# Register.net
KiCad netlist of a schematic drawn in EAGLE
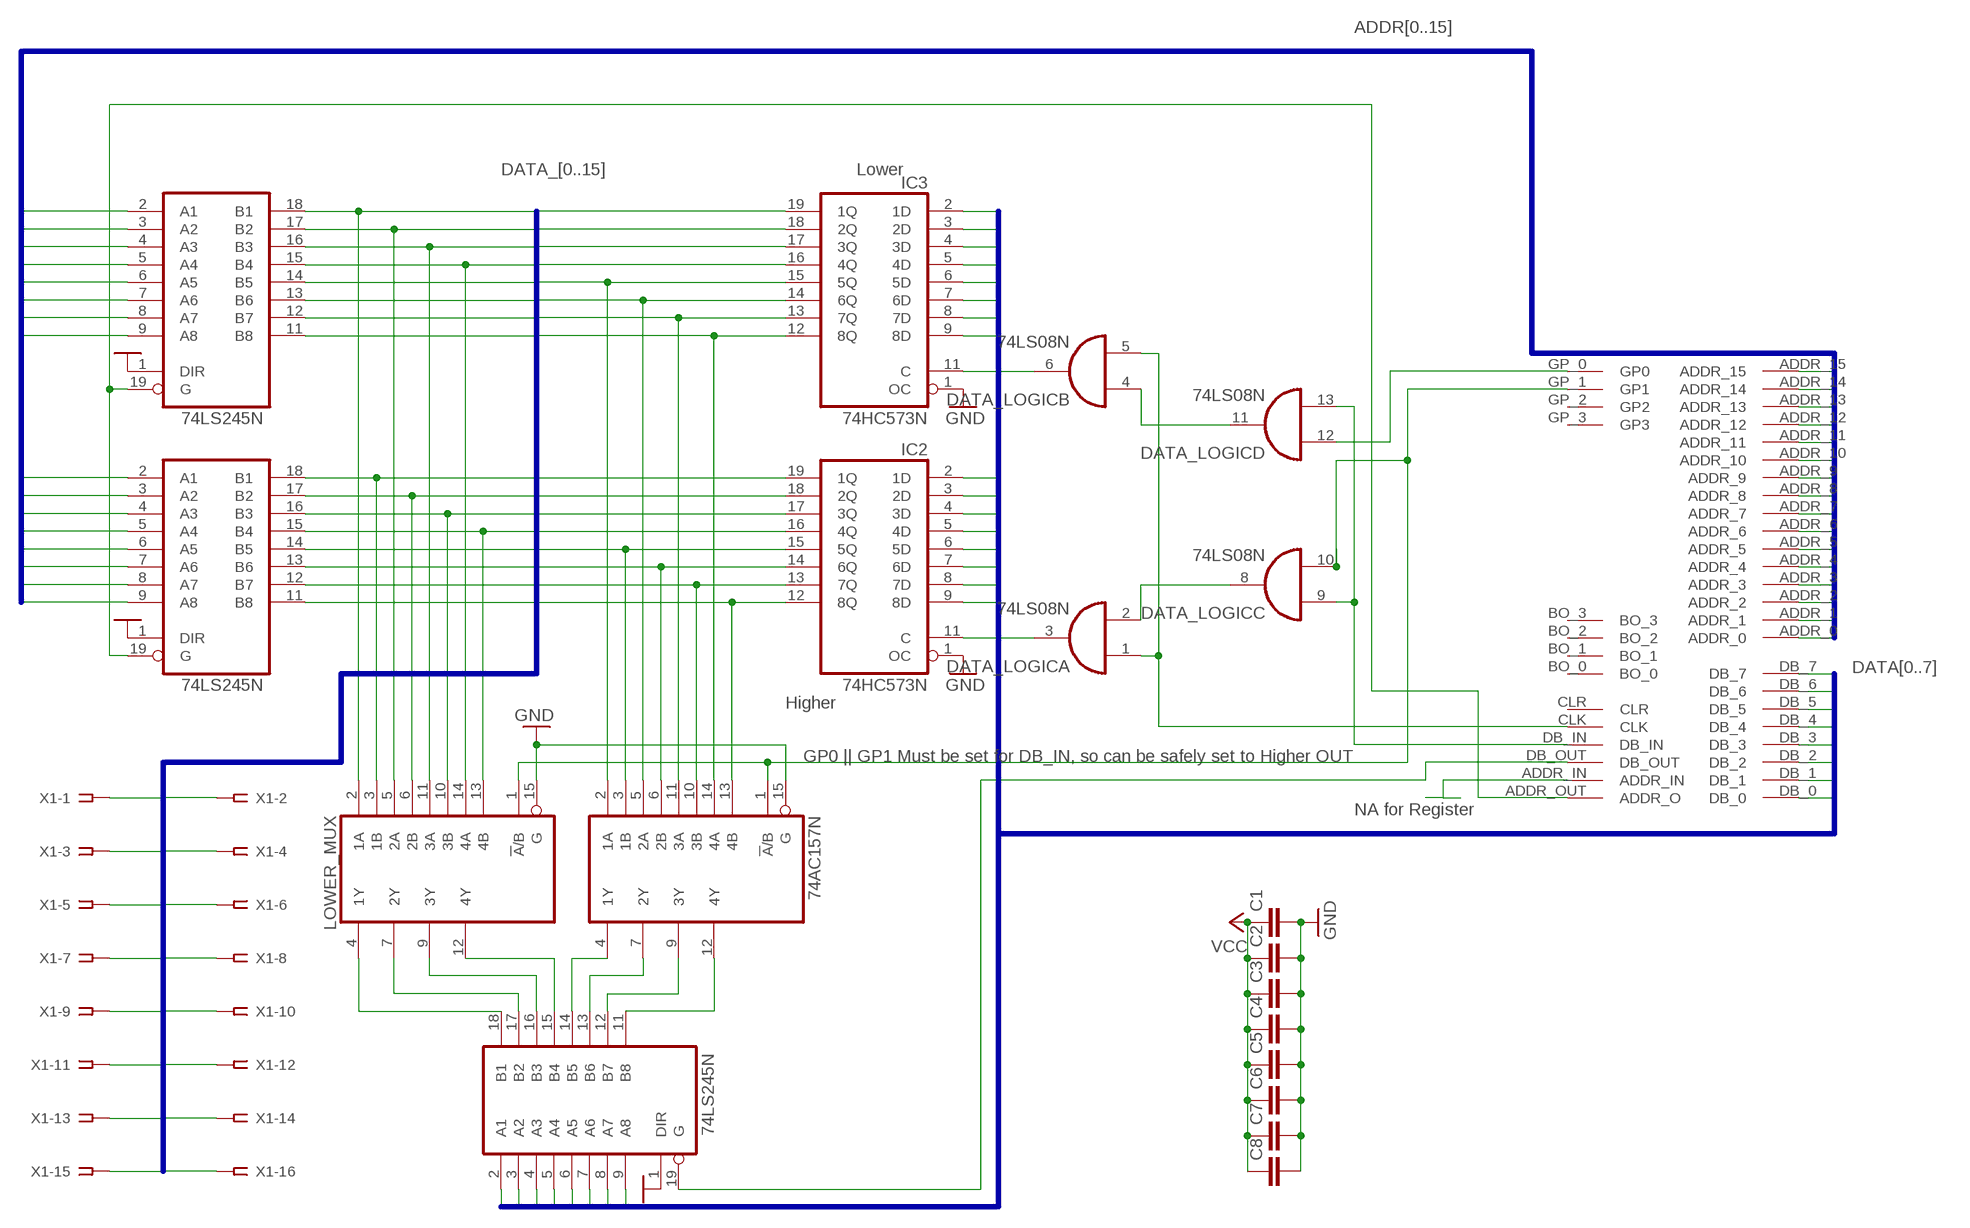
[diagram p0: schematic, sheet 1]

(export (version "E")
  (design (tool "Eeschema 10.0.6"))
  (components
    (comp (ref "ADDR_HIGHER_BUFFER")
      (value "74LS245N")
      (footprint "eagle-import:DIL20")
      (libsource (lib "eagle-import") (part "74245NLS"))
    )
    (comp (ref "ADDR_LOWER_BUFFER")
      (value "74LS245N")
      (footprint "eagle-import:DIL20")
      (libsource (lib "eagle-import") (part "74245NLS"))
    )
    (comp (ref "C1")
      (value "C2.5/2")
      (footprint "eagle-import:C2.5-2")
      (libsource (lib "eagle-import") (part "C2.5/2"))
    )
    (comp (ref "C2")
      (value "C2.5/2")
      (footprint "eagle-import:C2.5-2")
      (libsource (lib "eagle-import") (part "C2.5/2"))
    )
    (comp (ref "C3")
      (value "C2.5/2")
      (footprint "eagle-import:C2.5-2")
      (libsource (lib "eagle-import") (part "C2.5/2"))
    )
    (comp (ref "C4")
      (value "C2.5/2")
      (footprint "eagle-import:C2.5-2")
      (libsource (lib "eagle-import") (part "C2.5/2"))
    )
    (comp (ref "C5")
      (value "C2.5/2")
      (footprint "eagle-import:C2.5-2")
      (libsource (lib "eagle-import") (part "C2.5/2"))
    )
    (comp (ref "C6")
      (value "C2.5/2")
      (footprint "eagle-import:C2.5-2")
      (libsource (lib "eagle-import") (part "C2.5/2"))
    )
    (comp (ref "C7")
      (value "C2.5/2")
      (footprint "eagle-import:C2.5-2")
      (libsource (lib "eagle-import") (part "C2.5/2"))
    )
    (comp (ref "C8")
      (value "C2.5/2")
      (footprint "eagle-import:C2.5-2")
      (libsource (lib "eagle-import") (part "C2.5/2"))
    )
    (comp (ref "DATA_LOGIC")
      (value "74LS08N")
      (footprint "eagle-import:DIL14")
      (libsource (lib "eagle-import") (part "7408NLS"))
    )
    (comp (ref "DATA_OUTPUT_BUFFER")
      (value "74LS245N")
      (footprint "eagle-import:DIL20")
      (libsource (lib "eagle-import") (part "74245NLS"))
    )
    (comp (ref "HIGHER_MUX")
      (value "74AC157N")
      (footprint "eagle-import:DIL16")
      (libsource (lib "eagle-import") (part "74157NAC"))
    )
    (comp (ref "IC2")
      (value "74HC573N")
      (footprint "eagle-import:DIL20")
      (libsource (lib "eagle-import") (part "74573NHC"))
    )
    (comp (ref "IC3")
      (value "74HC573N")
      (footprint "eagle-import:DIL20")
      (libsource (lib "eagle-import") (part "74573NHC"))
    )
    (comp (ref "LOWER_MUX")
      (value "74AC157N")
      (footprint "eagle-import:DIL16")
      (libsource (lib "eagle-import") (part "74157NAC"))
    )
    (comp (ref "U$1")
      (value "BACKPLATE_INTERFACEEDGE_FINGER")
      (footprint "eagle-import:BACK_INTERFACE-FOOT")
      (libsource (lib "eagle-import") (part "BACKPLATE_INTERFACEEDGE_FINGER"))
    )
    (comp (ref "X1")
      (value "SSW-108-02-G-D")
      (footprint "eagle-import:SSW-108-02-G-D")
      (fields (field (name "MF") "Samtec Inc."))
      (libsource (lib "eagle-import") (part "SSW-108-02-G-D"))
    )
  )
  (nets
    (net (code "1") (name "/ADDR0") (class "Default")
      (node (ref "ADDR_LOWER_BUFFER") (pin "2") (pinfunction "A1_2") (pintype "bidirectional"))
      (node (ref "U$1") (pin "ADDR_0") (pinfunction "ADDR_0_ADDR_0") (pintype "bidirectional"))
    )
    (net (code "2") (name "/ADDR1") (class "Default")
      (node (ref "ADDR_LOWER_BUFFER") (pin "3") (pinfunction "A2_3") (pintype "bidirectional"))
      (node (ref "U$1") (pin "ADDR_1") (pinfunction "ADDR_1_ADDR_1") (pintype "bidirectional"))
    )
    (net (code "3") (name "/ADDR2") (class "Default")
      (node (ref "ADDR_LOWER_BUFFER") (pin "4") (pinfunction "A3_4") (pintype "bidirectional"))
      (node (ref "U$1") (pin "ADDR_2") (pinfunction "ADDR_2_ADDR_2") (pintype "bidirectional"))
    )
    (net (code "4") (name "/ADDR3") (class "Default")
      (node (ref "ADDR_LOWER_BUFFER") (pin "5") (pinfunction "A4_5") (pintype "bidirectional"))
      (node (ref "U$1") (pin "ADDR_3") (pinfunction "ADDR_3_ADDR_3") (pintype "bidirectional"))
    )
    (net (code "5") (name "/ADDR4") (class "Default")
      (node (ref "ADDR_LOWER_BUFFER") (pin "6") (pinfunction "A5_6") (pintype "bidirectional"))
      (node (ref "U$1") (pin "ADDR_4") (pinfunction "ADDR_4_ADDR_4") (pintype "bidirectional"))
    )
    (net (code "6") (name "/ADDR5") (class "Default")
      (node (ref "ADDR_LOWER_BUFFER") (pin "7") (pinfunction "A6_7") (pintype "bidirectional"))
      (node (ref "U$1") (pin "ADDR_5") (pinfunction "ADDR_5_ADDR_5") (pintype "bidirectional"))
    )
    (net (code "7") (name "/ADDR6") (class "Default")
      (node (ref "ADDR_LOWER_BUFFER") (pin "8") (pinfunction "A7_8") (pintype "bidirectional"))
      (node (ref "U$1") (pin "ADDR_6") (pinfunction "ADDR_6_ADDR_6") (pintype "bidirectional"))
    )
    (net (code "8") (name "/ADDR7") (class "Default")
      (node (ref "ADDR_LOWER_BUFFER") (pin "9") (pinfunction "A8_9") (pintype "bidirectional"))
      (node (ref "U$1") (pin "ADDR_7") (pinfunction "ADDR_7_ADDR_7") (pintype "bidirectional"))
    )
    (net (code "9") (name "/ADDR8") (class "Default")
      (node (ref "ADDR_HIGHER_BUFFER") (pin "2") (pinfunction "A1_2") (pintype "bidirectional"))
      (node (ref "U$1") (pin "ADDR_8") (pinfunction "ADDR_8_ADDR_8") (pintype "bidirectional"))
    )
    (net (code "10") (name "/ADDR9") (class "Default")
      (node (ref "ADDR_HIGHER_BUFFER") (pin "3") (pinfunction "A2_3") (pintype "bidirectional"))
      (node (ref "U$1") (pin "ADDR_9") (pinfunction "ADDR_9_ADDR_9") (pintype "bidirectional"))
    )
    (net (code "11") (name "/ADDR10") (class "Default")
      (node (ref "ADDR_HIGHER_BUFFER") (pin "4") (pinfunction "A3_4") (pintype "bidirectional"))
      (node (ref "U$1") (pin "ADDR_10") (pinfunction "ADDR_10_ADDR_10") (pintype "bidirectional"))
    )
    (net (code "12") (name "/ADDR11") (class "Default")
      (node (ref "ADDR_HIGHER_BUFFER") (pin "5") (pinfunction "A4_5") (pintype "bidirectional"))
      (node (ref "U$1") (pin "ADDR_11") (pinfunction "ADDR_11_ADDR_11") (pintype "bidirectional"))
    )
    (net (code "13") (name "/ADDR12") (class "Default")
      (node (ref "ADDR_HIGHER_BUFFER") (pin "6") (pinfunction "A5_6") (pintype "bidirectional"))
      (node (ref "U$1") (pin "ADDR_12") (pinfunction "ADDR_12_ADDR_12") (pintype "bidirectional"))
    )
    (net (code "14") (name "/ADDR13") (class "Default")
      (node (ref "ADDR_HIGHER_BUFFER") (pin "7") (pinfunction "A6_7") (pintype "bidirectional"))
      (node (ref "U$1") (pin "ADDR_13") (pinfunction "ADDR_13_ADDR_13") (pintype "bidirectional"))
    )
    (net (code "15") (name "/ADDR14") (class "Default")
      (node (ref "ADDR_HIGHER_BUFFER") (pin "8") (pinfunction "A7_8") (pintype "bidirectional"))
      (node (ref "U$1") (pin "ADDR_14") (pinfunction "ADDR_14_ADDR_14") (pintype "bidirectional"))
    )
    (net (code "16") (name "/ADDR15") (class "Default")
      (node (ref "ADDR_HIGHER_BUFFER") (pin "9") (pinfunction "A8_9") (pintype "bidirectional"))
      (node (ref "U$1") (pin "ADDR_15") (pinfunction "ADDR_15_ADDR_15") (pintype "bidirectional"))
    )
    (net (code "18") (name "/DATA0") (class "Default")
      (node (ref "DATA_OUTPUT_BUFFER") (pin "2") (pinfunction "A1_2") (pintype "bidirectional"))
      (node (ref "IC2") (pin "2") (pinfunction "1D_2") (pintype "input"))
      (node (ref "IC3") (pin "2") (pinfunction "1D_2") (pintype "input"))
      (node (ref "U$1") (pin "DB_0") (pinfunction "DB_0_DB_0") (pintype "bidirectional"))
    )
    (net (code "19") (name "/DATA1") (class "Default")
      (node (ref "DATA_OUTPUT_BUFFER") (pin "3") (pinfunction "A2_3") (pintype "bidirectional"))
      (node (ref "IC2") (pin "3") (pinfunction "2D_3") (pintype "input"))
      (node (ref "IC3") (pin "3") (pinfunction "2D_3") (pintype "input"))
      (node (ref "U$1") (pin "DB_1") (pinfunction "DB_1_DB_1") (pintype "bidirectional"))
    )
    (net (code "20") (name "/DATA2") (class "Default")
      (node (ref "DATA_OUTPUT_BUFFER") (pin "4") (pinfunction "A3_4") (pintype "bidirectional"))
      (node (ref "IC2") (pin "4") (pinfunction "3D_4") (pintype "input"))
      (node (ref "IC3") (pin "4") (pinfunction "3D_4") (pintype "input"))
      (node (ref "U$1") (pin "DB_2") (pinfunction "DB_2_DB_2") (pintype "bidirectional"))
    )
    (net (code "21") (name "/DATA3") (class "Default")
      (node (ref "DATA_OUTPUT_BUFFER") (pin "5") (pinfunction "A4_5") (pintype "bidirectional"))
      (node (ref "IC2") (pin "5") (pinfunction "4D_5") (pintype "input"))
      (node (ref "IC3") (pin "5") (pinfunction "4D_5") (pintype "input"))
      (node (ref "U$1") (pin "DB_3") (pinfunction "DB_3_DB_3") (pintype "bidirectional"))
    )
    (net (code "22") (name "/DATA4") (class "Default")
      (node (ref "DATA_OUTPUT_BUFFER") (pin "6") (pinfunction "A5_6") (pintype "bidirectional"))
      (node (ref "IC2") (pin "6") (pinfunction "5D_6") (pintype "input"))
      (node (ref "IC3") (pin "6") (pinfunction "5D_6") (pintype "input"))
      (node (ref "U$1") (pin "DB_4") (pinfunction "DB_4_DB_4") (pintype "bidirectional"))
    )
    (net (code "23") (name "/DATA5") (class "Default")
      (node (ref "DATA_OUTPUT_BUFFER") (pin "7") (pinfunction "A6_7") (pintype "bidirectional"))
      (node (ref "IC2") (pin "7") (pinfunction "6D_7") (pintype "input"))
      (node (ref "IC3") (pin "7") (pinfunction "6D_7") (pintype "input"))
      (node (ref "U$1") (pin "DB_5") (pinfunction "DB_5_DB_5") (pintype "bidirectional"))
    )
    (net (code "24") (name "/DATA6") (class "Default")
      (node (ref "DATA_OUTPUT_BUFFER") (pin "8") (pinfunction "A7_8") (pintype "bidirectional"))
      (node (ref "IC2") (pin "8") (pinfunction "7D_8") (pintype "input"))
      (node (ref "IC3") (pin "8") (pinfunction "7D_8") (pintype "input"))
      (node (ref "U$1") (pin "DB_6") (pinfunction "DB_6_DB_6") (pintype "bidirectional"))
    )
    (net (code "25") (name "/DATA7") (class "Default")
      (node (ref "DATA_OUTPUT_BUFFER") (pin "9") (pinfunction "A8_9") (pintype "bidirectional"))
      (node (ref "IC2") (pin "9") (pinfunction "8D_9") (pintype "input"))
      (node (ref "IC3") (pin "9") (pinfunction "8D_9") (pintype "input"))
      (node (ref "U$1") (pin "DB_7") (pinfunction "DB_7_DB_7") (pintype "bidirectional"))
    )
    (net (code "27") (name "/DATA_0") (class "Default")
      (node (ref "ADDR_LOWER_BUFFER") (pin "18") (pinfunction "B1_18") (pintype "bidirectional"))
      (node (ref "IC3") (pin "19") (pinfunction "1Q_19") (pintype "tri_state"))
      (node (ref "LOWER_MUX") (pin "2") (pinfunction "1A_2") (pintype "input"))
      (node (ref "X1") (pin "15") (pinfunction "1_15") (pintype "passive"))
    )
    (net (code "28") (name "/DATA_1") (class "Default")
      (node (ref "ADDR_LOWER_BUFFER") (pin "17") (pinfunction "B2_17") (pintype "bidirectional"))
      (node (ref "IC3") (pin "18") (pinfunction "2Q_18") (pintype "tri_state"))
      (node (ref "LOWER_MUX") (pin "5") (pinfunction "2A_5") (pintype "input"))
      (node (ref "X1") (pin "13") (pinfunction "1_13") (pintype "passive"))
    )
    (net (code "29") (name "/DATA_2") (class "Default")
      (node (ref "ADDR_LOWER_BUFFER") (pin "16") (pinfunction "B3_16") (pintype "bidirectional"))
      (node (ref "IC3") (pin "17") (pinfunction "3Q_17") (pintype "tri_state"))
      (node (ref "LOWER_MUX") (pin "11") (pinfunction "3A_11") (pintype "input"))
      (node (ref "X1") (pin "11") (pinfunction "1_11") (pintype "passive"))
    )
    (net (code "30") (name "/DATA_3") (class "Default")
      (node (ref "ADDR_LOWER_BUFFER") (pin "15") (pinfunction "B4_15") (pintype "bidirectional"))
      (node (ref "IC3") (pin "16") (pinfunction "4Q_16") (pintype "tri_state"))
      (node (ref "LOWER_MUX") (pin "14") (pinfunction "4A_14") (pintype "input"))
      (node (ref "X1") (pin "9") (pinfunction "1_9") (pintype "passive"))
    )
    (net (code "31") (name "/DATA_4") (class "Default")
      (node (ref "ADDR_LOWER_BUFFER") (pin "14") (pinfunction "B5_14") (pintype "bidirectional"))
      (node (ref "HIGHER_MUX") (pin "2") (pinfunction "1A_2") (pintype "input"))
      (node (ref "IC3") (pin "15") (pinfunction "5Q_15") (pintype "tri_state"))
      (node (ref "X1") (pin "7") (pinfunction "1_7") (pintype "passive"))
    )
    (net (code "32") (name "/DATA_5") (class "Default")
      (node (ref "ADDR_LOWER_BUFFER") (pin "13") (pinfunction "B6_13") (pintype "bidirectional"))
      (node (ref "HIGHER_MUX") (pin "5") (pinfunction "2A_5") (pintype "input"))
      (node (ref "IC3") (pin "14") (pinfunction "6Q_14") (pintype "tri_state"))
      (node (ref "X1") (pin "5") (pinfunction "1_5") (pintype "passive"))
    )
    (net (code "33") (name "/DATA_6") (class "Default")
      (node (ref "ADDR_LOWER_BUFFER") (pin "12") (pinfunction "B7_12") (pintype "bidirectional"))
      (node (ref "HIGHER_MUX") (pin "11") (pinfunction "3A_11") (pintype "input"))
      (node (ref "IC3") (pin "13") (pinfunction "7Q_13") (pintype "tri_state"))
      (node (ref "X1") (pin "3") (pinfunction "1_3") (pintype "passive"))
    )
    (net (code "34") (name "/DATA_7") (class "Default")
      (node (ref "ADDR_LOWER_BUFFER") (pin "11") (pinfunction "B8_11") (pintype "bidirectional"))
      (node (ref "HIGHER_MUX") (pin "14") (pinfunction "4A_14") (pintype "input"))
      (node (ref "IC3") (pin "12") (pinfunction "8Q_12") (pintype "tri_state"))
      (node (ref "X1") (pin "1") (pinfunction "1_1") (pintype "passive"))
    )
    (net (code "35") (name "/DATA_8") (class "Default")
      (node (ref "ADDR_HIGHER_BUFFER") (pin "18") (pinfunction "B1_18") (pintype "bidirectional"))
      (node (ref "IC2") (pin "19") (pinfunction "1Q_19") (pintype "tri_state"))
      (node (ref "LOWER_MUX") (pin "3") (pinfunction "1B_3") (pintype "input"))
      (node (ref "X1") (pin "2") (pinfunction "1_2") (pintype "passive"))
    )
    (net (code "36") (name "/DATA_9") (class "Default")
      (node (ref "ADDR_HIGHER_BUFFER") (pin "17") (pinfunction "B2_17") (pintype "bidirectional"))
      (node (ref "IC2") (pin "18") (pinfunction "2Q_18") (pintype "tri_state"))
      (node (ref "LOWER_MUX") (pin "6") (pinfunction "2B_6") (pintype "input"))
      (node (ref "X1") (pin "4") (pinfunction "1_4") (pintype "passive"))
    )
    (net (code "37") (name "/DATA_10") (class "Default")
      (node (ref "ADDR_HIGHER_BUFFER") (pin "16") (pinfunction "B3_16") (pintype "bidirectional"))
      (node (ref "IC2") (pin "17") (pinfunction "3Q_17") (pintype "tri_state"))
      (node (ref "LOWER_MUX") (pin "10") (pinfunction "3B_10") (pintype "input"))
      (node (ref "X1") (pin "6") (pinfunction "1_6") (pintype "passive"))
    )
    (net (code "38") (name "/DATA_11") (class "Default")
      (node (ref "ADDR_HIGHER_BUFFER") (pin "15") (pinfunction "B4_15") (pintype "bidirectional"))
      (node (ref "IC2") (pin "16") (pinfunction "4Q_16") (pintype "tri_state"))
      (node (ref "LOWER_MUX") (pin "13") (pinfunction "4B_13") (pintype "input"))
      (node (ref "X1") (pin "8") (pinfunction "1_8") (pintype "passive"))
    )
    (net (code "39") (name "/DATA_12") (class "Default")
      (node (ref "ADDR_HIGHER_BUFFER") (pin "14") (pinfunction "B5_14") (pintype "bidirectional"))
      (node (ref "HIGHER_MUX") (pin "3") (pinfunction "1B_3") (pintype "input"))
      (node (ref "IC2") (pin "15") (pinfunction "5Q_15") (pintype "tri_state"))
      (node (ref "X1") (pin "10") (pinfunction "1_10") (pintype "passive"))
    )
    (net (code "40") (name "/DATA_13") (class "Default")
      (node (ref "ADDR_HIGHER_BUFFER") (pin "13") (pinfunction "B6_13") (pintype "bidirectional"))
      (node (ref "HIGHER_MUX") (pin "6") (pinfunction "2B_6") (pintype "input"))
      (node (ref "IC2") (pin "14") (pinfunction "6Q_14") (pintype "tri_state"))
      (node (ref "X1") (pin "12") (pinfunction "1_12") (pintype "passive"))
    )
    (net (code "41") (name "/DATA_14") (class "Default")
      (node (ref "ADDR_HIGHER_BUFFER") (pin "12") (pinfunction "B7_12") (pintype "bidirectional"))
      (node (ref "HIGHER_MUX") (pin "10") (pinfunction "3B_10") (pintype "input"))
      (node (ref "IC2") (pin "13") (pinfunction "7Q_13") (pintype "tri_state"))
      (node (ref "X1") (pin "14") (pinfunction "1_14") (pintype "passive"))
    )
    (net (code "42") (name "/DATA_15") (class "Default")
      (node (ref "ADDR_HIGHER_BUFFER") (pin "11") (pinfunction "B8_11") (pintype "bidirectional"))
      (node (ref "HIGHER_MUX") (pin "13") (pinfunction "4B_13") (pintype "input"))
      (node (ref "IC2") (pin "12") (pinfunction "8Q_12") (pintype "tri_state"))
      (node (ref "X1") (pin "16") (pinfunction "1_16") (pintype "passive"))
    )
    (net (code "43") (name "GND") (class "Default")
      (node (ref "ADDR_HIGHER_BUFFER") (pin "1") (pinfunction "DIR_1") (pintype "input"))
      (node (ref "ADDR_LOWER_BUFFER") (pin "1") (pinfunction "DIR_1") (pintype "input"))
      (node (ref "C1") (pin "2") (pinfunction "2_2") (pintype "passive"))
      (node (ref "C2") (pin "2") (pinfunction "2_2") (pintype "passive"))
      (node (ref "C3") (pin "2") (pinfunction "2_2") (pintype "passive"))
      (node (ref "C4") (pin "2") (pinfunction "2_2") (pintype "passive"))
      (node (ref "C5") (pin "2") (pinfunction "2_2") (pintype "passive"))
      (node (ref "C6") (pin "2") (pinfunction "2_2") (pintype "passive"))
      (node (ref "C7") (pin "2") (pinfunction "2_2") (pintype "passive"))
      (node (ref "C8") (pin "2") (pinfunction "2_2") (pintype "passive"))
      (node (ref "DATA_OUTPUT_BUFFER") (pin "1") (pinfunction "DIR_1") (pintype "input"))
      (node (ref "HIGHER_MUX") (pin "15") (pinfunction "G_15") (pintype "input"))
      (node (ref "IC2") (pin "1") (pinfunction "OC_1") (pintype "input"))
      (node (ref "IC3") (pin "1") (pinfunction "OC_1") (pintype "input"))
      (node (ref "LOWER_MUX") (pin "15") (pinfunction "G_15") (pintype "input"))
    )
    (net (code "44") (name "Net-(ADDR_HIGHER_BUFFERA-G)") (class "Default")
      (node (ref "ADDR_HIGHER_BUFFER") (pin "19") (pinfunction "G_19") (pintype "input"))
      (node (ref "ADDR_LOWER_BUFFER") (pin "19") (pinfunction "G_19") (pintype "input"))
      (node (ref "U$1") (pin "ADDR_OUT") (pinfunction "ADDR_O_ADDR_OUT") (pintype "bidirectional"))
    )
    (net (code "45") (name "Net-(DATA_LOGICA-I0)") (class "Default")
      (node (ref "DATA_LOGIC") (pin "1") (pinfunction "I0_1") (pintype "input"))
      (node (ref "DATA_LOGIC") (pin "5") (pinfunction "I1_5") (pintype "input"))
      (node (ref "U$1") (pin "CLK") (pinfunction "CLK_CLK") (pintype "bidirectional"))
    )
    (net (code "46") (name "Net-(DATA_LOGICA-I1)") (class "Default")
      (node (ref "DATA_LOGIC") (pin "2") (pinfunction "I1_2") (pintype "input"))
      (node (ref "DATA_LOGIC") (pin "8") (pinfunction "O_8") (pintype "output"))
    )
    (net (code "47") (name "Net-(DATA_LOGICA-O)") (class "Default")
      (node (ref "DATA_LOGIC") (pin "3") (pinfunction "O_3") (pintype "output"))
      (node (ref "IC2") (pin "11") (pinfunction "C_11") (pintype "input"))
    )
    (net (code "48") (name "Net-(DATA_LOGICB-I0)") (class "Default")
      (node (ref "DATA_LOGIC") (pin "11") (pinfunction "O_11") (pintype "output"))
      (node (ref "DATA_LOGIC") (pin "4") (pinfunction "I0_4") (pintype "input"))
    )
    (net (code "49") (name "Net-(DATA_LOGICB-O)") (class "Default")
      (node (ref "DATA_LOGIC") (pin "6") (pinfunction "O_6") (pintype "output"))
      (node (ref "IC3") (pin "11") (pinfunction "C_11") (pintype "input"))
    )
    (net (code "50") (name "Net-(DATA_LOGICC-I0)") (class "Default")
      (node (ref "DATA_LOGIC") (pin "13") (pinfunction "I1_13") (pintype "input"))
      (node (ref "DATA_LOGIC") (pin "9") (pinfunction "I0_9") (pintype "input"))
      (node (ref "U$1") (pin "DB_IN") (pinfunction "DB_IN_DB_IN") (pintype "bidirectional"))
    )
    (net (code "51") (name "Net-(DATA_LOGICC-I1)") (class "Default")
      (node (ref "DATA_LOGIC") (pin "10") (pinfunction "I1_10") (pintype "input"))
      (node (ref "HIGHER_MUX") (pin "1") (pinfunction "~{A}/B_1") (pintype "input"))
      (node (ref "LOWER_MUX") (pin "1") (pinfunction "~{A}/B_1") (pintype "input"))
      (node (ref "U$1") (pin "GP_1") (pinfunction "GP1_GP_1") (pintype "bidirectional"))
    )
    (net (code "52") (name "Net-(DATA_LOGICD-I0)") (class "Default")
      (node (ref "DATA_LOGIC") (pin "12") (pinfunction "I0_12") (pintype "input"))
      (node (ref "U$1") (pin "GP_0") (pinfunction "GP0_GP_0") (pintype "bidirectional"))
    )
    (net (code "53") (name "Net-(DATA_OUTPUT_BUFFERA-B1)") (class "Default")
      (node (ref "DATA_OUTPUT_BUFFER") (pin "18") (pinfunction "B1_18") (pintype "bidirectional"))
      (node (ref "LOWER_MUX") (pin "4") (pinfunction "1Y_4") (pintype "output"))
    )
    (net (code "54") (name "Net-(DATA_OUTPUT_BUFFERA-B2)") (class "Default")
      (node (ref "DATA_OUTPUT_BUFFER") (pin "17") (pinfunction "B2_17") (pintype "bidirectional"))
      (node (ref "LOWER_MUX") (pin "7") (pinfunction "2Y_7") (pintype "output"))
    )
    (net (code "55") (name "Net-(DATA_OUTPUT_BUFFERA-B3)") (class "Default")
      (node (ref "DATA_OUTPUT_BUFFER") (pin "16") (pinfunction "B3_16") (pintype "bidirectional"))
      (node (ref "LOWER_MUX") (pin "9") (pinfunction "3Y_9") (pintype "output"))
    )
    (net (code "56") (name "Net-(DATA_OUTPUT_BUFFERA-B4)") (class "Default")
      (node (ref "DATA_OUTPUT_BUFFER") (pin "15") (pinfunction "B4_15") (pintype "bidirectional"))
      (node (ref "LOWER_MUX") (pin "12") (pinfunction "4Y_12") (pintype "output"))
    )
    (net (code "57") (name "Net-(DATA_OUTPUT_BUFFERA-B5)") (class "Default")
      (node (ref "DATA_OUTPUT_BUFFER") (pin "14") (pinfunction "B5_14") (pintype "bidirectional"))
      (node (ref "HIGHER_MUX") (pin "4") (pinfunction "1Y_4") (pintype "output"))
    )
    (net (code "58") (name "Net-(DATA_OUTPUT_BUFFERA-B6)") (class "Default")
      (node (ref "DATA_OUTPUT_BUFFER") (pin "13") (pinfunction "B6_13") (pintype "bidirectional"))
      (node (ref "HIGHER_MUX") (pin "7") (pinfunction "2Y_7") (pintype "output"))
    )
    (net (code "59") (name "Net-(DATA_OUTPUT_BUFFERA-B7)") (class "Default")
      (node (ref "DATA_OUTPUT_BUFFER") (pin "12") (pinfunction "B7_12") (pintype "bidirectional"))
      (node (ref "HIGHER_MUX") (pin "9") (pinfunction "3Y_9") (pintype "output"))
    )
    (net (code "60") (name "Net-(DATA_OUTPUT_BUFFERA-B8)") (class "Default")
      (node (ref "DATA_OUTPUT_BUFFER") (pin "11") (pinfunction "B8_11") (pintype "bidirectional"))
      (node (ref "HIGHER_MUX") (pin "12") (pinfunction "4Y_12") (pintype "output"))
    )
    (net (code "61") (name "Net-(DATA_OUTPUT_BUFFERA-G)") (class "Default")
      (node (ref "DATA_OUTPUT_BUFFER") (pin "19") (pinfunction "G_19") (pintype "input"))
      (node (ref "U$1") (pin "DB_OUT") (pinfunction "DB_OUT_DB_OUT") (pintype "bidirectional"))
    )
    (net (code "62") (name "VCC") (class "Default")
      (node (ref "C1") (pin "1") (pinfunction "1_1") (pintype "passive"))
      (node (ref "C2") (pin "1") (pinfunction "1_1") (pintype "passive"))
      (node (ref "C3") (pin "1") (pinfunction "1_1") (pintype "passive"))
      (node (ref "C4") (pin "1") (pinfunction "1_1") (pintype "passive"))
      (node (ref "C5") (pin "1") (pinfunction "1_1") (pintype "passive"))
      (node (ref "C6") (pin "1") (pinfunction "1_1") (pintype "passive"))
      (node (ref "C7") (pin "1") (pinfunction "1_1") (pintype "passive"))
      (node (ref "C8") (pin "1") (pinfunction "1_1") (pintype "passive"))
    )
    (net (code "63") (name "unconnected-(U$1-PadADDR_IN)") (class "Default")
      (node (ref "U$1") (pin "ADDR_IN") (pinfunction "ADDR_IN_ADDR_IN") (pintype "bidirectional"))
    )
    (net (code "64") (name "unconnected-(U$1-PadBO_0)") (class "Default")
      (node (ref "U$1") (pin "BO_0") (pinfunction "BO_0_BO_0") (pintype "bidirectional"))
    )
    (net (code "65") (name "unconnected-(U$1-PadBO_1)") (class "Default")
      (node (ref "U$1") (pin "BO_1") (pinfunction "BO_1_BO_1") (pintype "bidirectional"))
    )
    (net (code "66") (name "unconnected-(U$1-PadBO_2)") (class "Default")
      (node (ref "U$1") (pin "BO_2") (pinfunction "BO_2_BO_2") (pintype "bidirectional"))
    )
    (net (code "67") (name "unconnected-(U$1-PadBO_3)") (class "Default")
      (node (ref "U$1") (pin "BO_3") (pinfunction "BO_3_BO_3") (pintype "bidirectional"))
    )
    (net (code "68") (name "unconnected-(U$1-PadCLR)") (class "Default")
      (node (ref "U$1") (pin "CLR") (pinfunction "CLR_CLR") (pintype "bidirectional"))
    )
    (net (code "69") (name "unconnected-(U$1A-GP2-PadGP_2)") (class "Default")
      (node (ref "U$1") (pin "GP_2") (pinfunction "GP2_GP_2") (pintype "bidirectional"))
    )
    (net (code "70") (name "unconnected-(U$1A-GP3-PadGP_3)") (class "Default")
      (node (ref "U$1") (pin "GP_3") (pinfunction "GP3_GP_3") (pintype "bidirectional"))
    )
  )
)
